# 5-Radio.net
KiCad netlist of a schematic drawn in Altium Designer
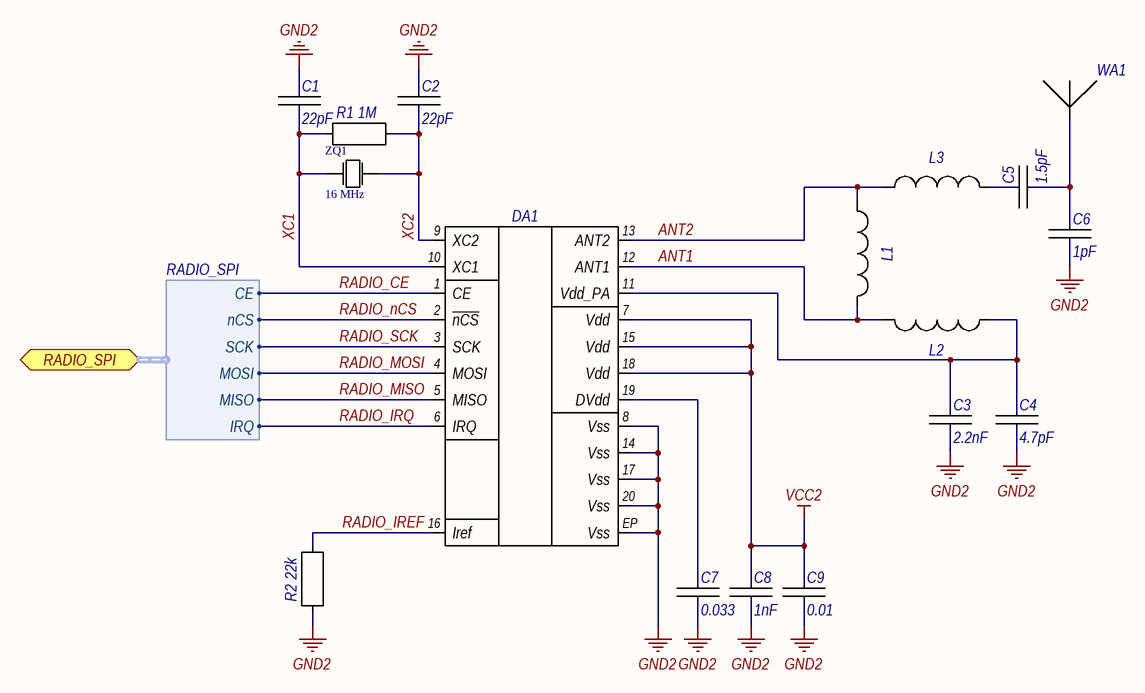
[diagram p0: 5-Radio.SchDoc]

(export (version "E")
  (design (tool "Eeschema 10.0.6"))
  (components
    (comp (ref "C1")
      (value "22pF")
      (footprint "CHIP_0402_C")
      (description "Конденсатор")
      (fields (field (name "PARTNUMBER") "CC0402JRNPO9BN220") (field (name "MFG") "YAGEO"))
      (libsource (lib "RCL") (part "Конденсатор"))
    )
    (comp (ref "C2")
      (value "22pF")
      (footprint "CHIP_0402_C")
      (description "Конденсатор")
      (fields (field (name "PARTNUMBER") "CC0402JRNPO9BN220") (field (name "MFG") "YAGEO"))
      (libsource (lib "RCL") (part "Конденсатор"))
    )
    (comp (ref "C3")
      (value "2.2nF")
      (footprint "CHIP_0402_C")
      (description "Конденсатор")
      (fields (field (name "PARTNUMBER") "GRM155R71H222KA01D") (field (name "MFG") "MURATA"))
      (libsource (lib "RCL") (part "Конденсатор"))
    )
    (comp (ref "C4")
      (value "4.7pF")
      (footprint "CHIP_0402_C")
      (description "Конденсатор")
      (fields (field (name "PARTNUMBER") "CC0402BRNPO9BN4R7") (field (name "MFG") "YAGEO"))
      (libsource (lib "RCL") (part "Конденсатор"))
    )
    (comp (ref "C5")
      (value "1.5pF")
      (footprint "CHIP_0402_C")
      (description "Конденсатор")
      (fields (field (name "PARTNUMBER") "CC0402CRNPO9BN1R5") (field (name "MFG") "YAGEO"))
      (libsource (lib "RCL") (part "Конденсатор"))
    )
    (comp (ref "C6")
      (value "1pF")
      (footprint "CHIP_0402_C")
      (description "Конденсатор")
      (fields (field (name "PARTNUMBER") "CC0402BRNPO9BNR50") (field (name "MFG") "YAGEO"))
      (libsource (lib "RCL") (part "Конденсатор"))
    )
    (comp (ref "C7")
      (value "0.033")
      (footprint "CHIP_0402_C")
      (description "Конденсатор")
      (fields (field (name "PARTNUMBER") "CC0402KRX7R7BB333") (field (name "MFG") "YAGEO"))
      (libsource (lib "RCL") (part "Конденсатор"))
    )
    (comp (ref "C8")
      (value "1nF")
      (footprint "CHIP_0402_C")
      (description "Конденсатор")
      (fields (field (name "PARTNUMBER") "CC0402JRNPO9BN102") (field (name "MFG") "YAGEO"))
      (libsource (lib "RCL") (part "Конденсатор"))
    )
    (comp (ref "C9")
      (value "0.01")
      (footprint "CHIP_0402_C")
      (description "Конденсатор")
      (fields (field (name "PARTNUMBER") "CC0402KRX7R9BB103") (field (name "MFG") "YAGEO"))
      (libsource (lib "RCL") (part "Конденсатор"))
    )
    (comp (ref "DA1")
      (value "nRF24L01+")
      (footprint "QFN-20 - DIY")
      (description "RF, 2.4 GHz Transceiver")
      (fields (field (name "MFG") "NORDIC SEMI"))
      (libsource (lib "ic") (part "nRF24L01+"))
    )
    (comp (ref "L1")
      (value "Дроссель")
      (footprint "CHIP_0402_L")
      (fields (field (name "PARTNUMBER") "LQW15AN8N2G00D") (field (name "MFG") "MURATA"))
      (libsource (lib "RCL") (part "Дроссель"))
    )
    (comp (ref "L2")
      (value "Дроссель")
      (footprint "CHIP_0402_L")
      (fields (field (name "PARTNUMBER") "LQG15HS27NJ02D") (field (name "MFG") "MURATA"))
      (libsource (lib "") (part "Дроссель_1"))
    )
    (comp (ref "L3")
      (value "Дроссель")
      (footprint "CHIP_0402_L")
      (fields (field (name "PARTNUMBER") "LQG15HN3N9S02D") (field (name "MFG") "MURATA"))
      (libsource (lib "RCL") (part "Дроссель"))
    )
    (comp (ref "R1")
      (value "1M")
      (footprint "CHIP_0402_R")
      (description "Резистор")
      (fields (field (name "PARTNUMBER") "RC0402FR-071ML") (field (name "MFG") "YAGEO"))
      (libsource (lib "RCL") (part "Резистор"))
    )
    (comp (ref "R2")
      (value "22k")
      (footprint "CHIP_0402_R")
      (description "Резистор")
      (fields (field (name "PARTNUMBER") "RC0402FR-0722KL") (field (name "MFG") "YAGEO"))
      (libsource (lib "RCL") (part "Резистор"))
    )
    (comp (ref "WA1")
      (value "Antenna")
      (footprint "ANTENNA PCB 2.4")
      (libsource (lib "el_mech") (part "Antenna"))
    )
    (comp (ref "ZQ1")
      (value "16 MHz")
      (footprint "HC-49SM")
      (description "Осциллятор, 2 вывода")
      (fields (field (name "PARTNUMBER") "16000 KHz HC-49/US"))
      (libsource (lib "el_mech") (part "XTAL_2pin"))
    )
  )
  (nets
    (net (code "2") (name "/ANT1") (class "Default")
      (node (ref "DA1") (pin "12") (pinfunction "ANT1_12") (pintype "passive"))
      (node (ref "L1") (pin "1") (pinfunction "1_1") (pintype "passive"))
      (node (ref "L2") (pin "2") (pinfunction "2_2") (pintype "passive"))
    )
    (net (code "3") (name "/ANT2") (class "Default")
      (node (ref "DA1") (pin "13") (pinfunction "ANT2_13") (pintype "passive"))
      (node (ref "L1") (pin "2") (pinfunction "2_2") (pintype "passive"))
      (node (ref "L3") (pin "2") (pinfunction "2_2") (pintype "passive"))
    )
    (net (code "4") (name "/RADIO_CE") (class "Default")
      (node (ref "DA1") (pin "1") (pinfunction "CE_1") (pintype "passive"))
    )
    (net (code "5") (name "/RADIO_IREF") (class "Default")
      (node (ref "DA1") (pin "16") (pinfunction "Iref_16") (pintype "passive"))
      (node (ref "R2") (pin "2") (pinfunction "2_2") (pintype "passive"))
    )
    (net (code "6") (name "/RADIO_IRQ") (class "Default")
      (node (ref "DA1") (pin "6") (pinfunction "IRQ_6") (pintype "passive"))
    )
    (net (code "7") (name "/RADIO_MISO") (class "Default")
      (node (ref "DA1") (pin "5") (pinfunction "MISO_5") (pintype "passive"))
    )
    (net (code "8") (name "/RADIO_MOSI") (class "Default")
      (node (ref "DA1") (pin "4") (pinfunction "MOSI_4") (pintype "passive"))
    )
    (net (code "9") (name "/RADIO_SCK") (class "Default")
      (node (ref "DA1") (pin "3") (pinfunction "SCK_3") (pintype "passive"))
    )
    (net (code "10") (name "/RADIO_nCS") (class "Default")
      (node (ref "DA1") (pin "2") (pinfunction "nCS_2") (pintype "passive"))
    )
    (net (code "11") (name "/XC1") (class "Default")
      (node (ref "C1") (pin "1") (pinfunction "1_1") (pintype "passive"))
      (node (ref "DA1") (pin "10") (pinfunction "XC1_10") (pintype "passive"))
      (node (ref "R1") (pin "1") (pinfunction "1_1") (pintype "passive"))
      (node (ref "ZQ1") (pin "1") (pinfunction "1_1") (pintype "passive"))
    )
    (net (code "12") (name "/XC2") (class "Default")
      (node (ref "C2") (pin "1") (pinfunction "1_1") (pintype "passive"))
      (node (ref "DA1") (pin "9") (pinfunction "XC2_9") (pintype "passive"))
      (node (ref "R1") (pin "2") (pinfunction "2_2") (pintype "passive"))
      (node (ref "ZQ1") (pin "2") (pinfunction "2_2") (pintype "passive"))
    )
    (net (code "14") (name "GND2") (class "Default")
      (node (ref "C1") (pin "2") (pinfunction "2_2") (pintype "passive"))
      (node (ref "C2") (pin "2") (pinfunction "2_2") (pintype "passive"))
      (node (ref "C3") (pin "1") (pinfunction "1_1") (pintype "passive"))
      (node (ref "C4") (pin "1") (pinfunction "1_1") (pintype "passive"))
      (node (ref "C6") (pin "1") (pinfunction "1_1") (pintype "passive"))
      (node (ref "C7") (pin "1") (pinfunction "1_1") (pintype "passive"))
      (node (ref "C8") (pin "1") (pinfunction "1_1") (pintype "passive"))
      (node (ref "C9") (pin "1") (pinfunction "1_1") (pintype "passive"))
      (node (ref "DA1") (pin "14") (pinfunction "Vss_14") (pintype "passive"))
      (node (ref "DA1") (pin "17") (pinfunction "Vss_17") (pintype "passive"))
      (node (ref "DA1") (pin "20") (pinfunction "Vss_20") (pintype "passive"))
      (node (ref "DA1") (pin "8") (pinfunction "Vss_8") (pintype "passive"))
      (node (ref "DA1") (pin "EP") (pinfunction "Vss_EP") (pintype "passive"))
      (node (ref "R2") (pin "1") (pinfunction "1_1") (pintype "passive"))
    )
    (net (code "15") (name "Net-(C5-Pad1)") (class "Default")
      (node (ref "C5") (pin "1") (pinfunction "1_1") (pintype "passive"))
      (node (ref "C6") (pin "2") (pinfunction "2_2") (pintype "passive"))
      (node (ref "WA1") (pin "1") (pinfunction "1_1") (pintype "passive"))
    )
    (net (code "16") (name "Net-(C5-Pad2)") (class "Default")
      (node (ref "C5") (pin "2") (pinfunction "2_2") (pintype "passive"))
      (node (ref "L3") (pin "1") (pinfunction "1_1") (pintype "passive"))
    )
    (net (code "17") (name "Net-(DA1-DVdd)") (class "Default")
      (node (ref "C7") (pin "2") (pinfunction "2_2") (pintype "passive"))
      (node (ref "DA1") (pin "19") (pinfunction "DVdd_19") (pintype "passive"))
    )
    (net (code "18") (name "Net-(DA1-Vdd_PA)") (class "Default")
      (node (ref "C3") (pin "2") (pinfunction "2_2") (pintype "passive"))
      (node (ref "C4") (pin "2") (pinfunction "2_2") (pintype "passive"))
      (node (ref "DA1") (pin "11") (pinfunction "Vdd_PA_11") (pintype "passive"))
      (node (ref "L2") (pin "1") (pinfunction "1_1") (pintype "passive"))
    )
    (net (code "19") (name "VCC2") (class "Default")
      (node (ref "C8") (pin "2") (pinfunction "2_2") (pintype "passive"))
      (node (ref "C9") (pin "2") (pinfunction "2_2") (pintype "passive"))
      (node (ref "DA1") (pin "15") (pinfunction "Vdd_15") (pintype "passive"))
      (node (ref "DA1") (pin "18") (pinfunction "Vdd_18") (pintype "passive"))
      (node (ref "DA1") (pin "7") (pinfunction "Vdd_7") (pintype "passive"))
    )
  )
)
